# IQOV-162_Evo_Board.net
KiCad netlist of a schematic drawn in EAGLE
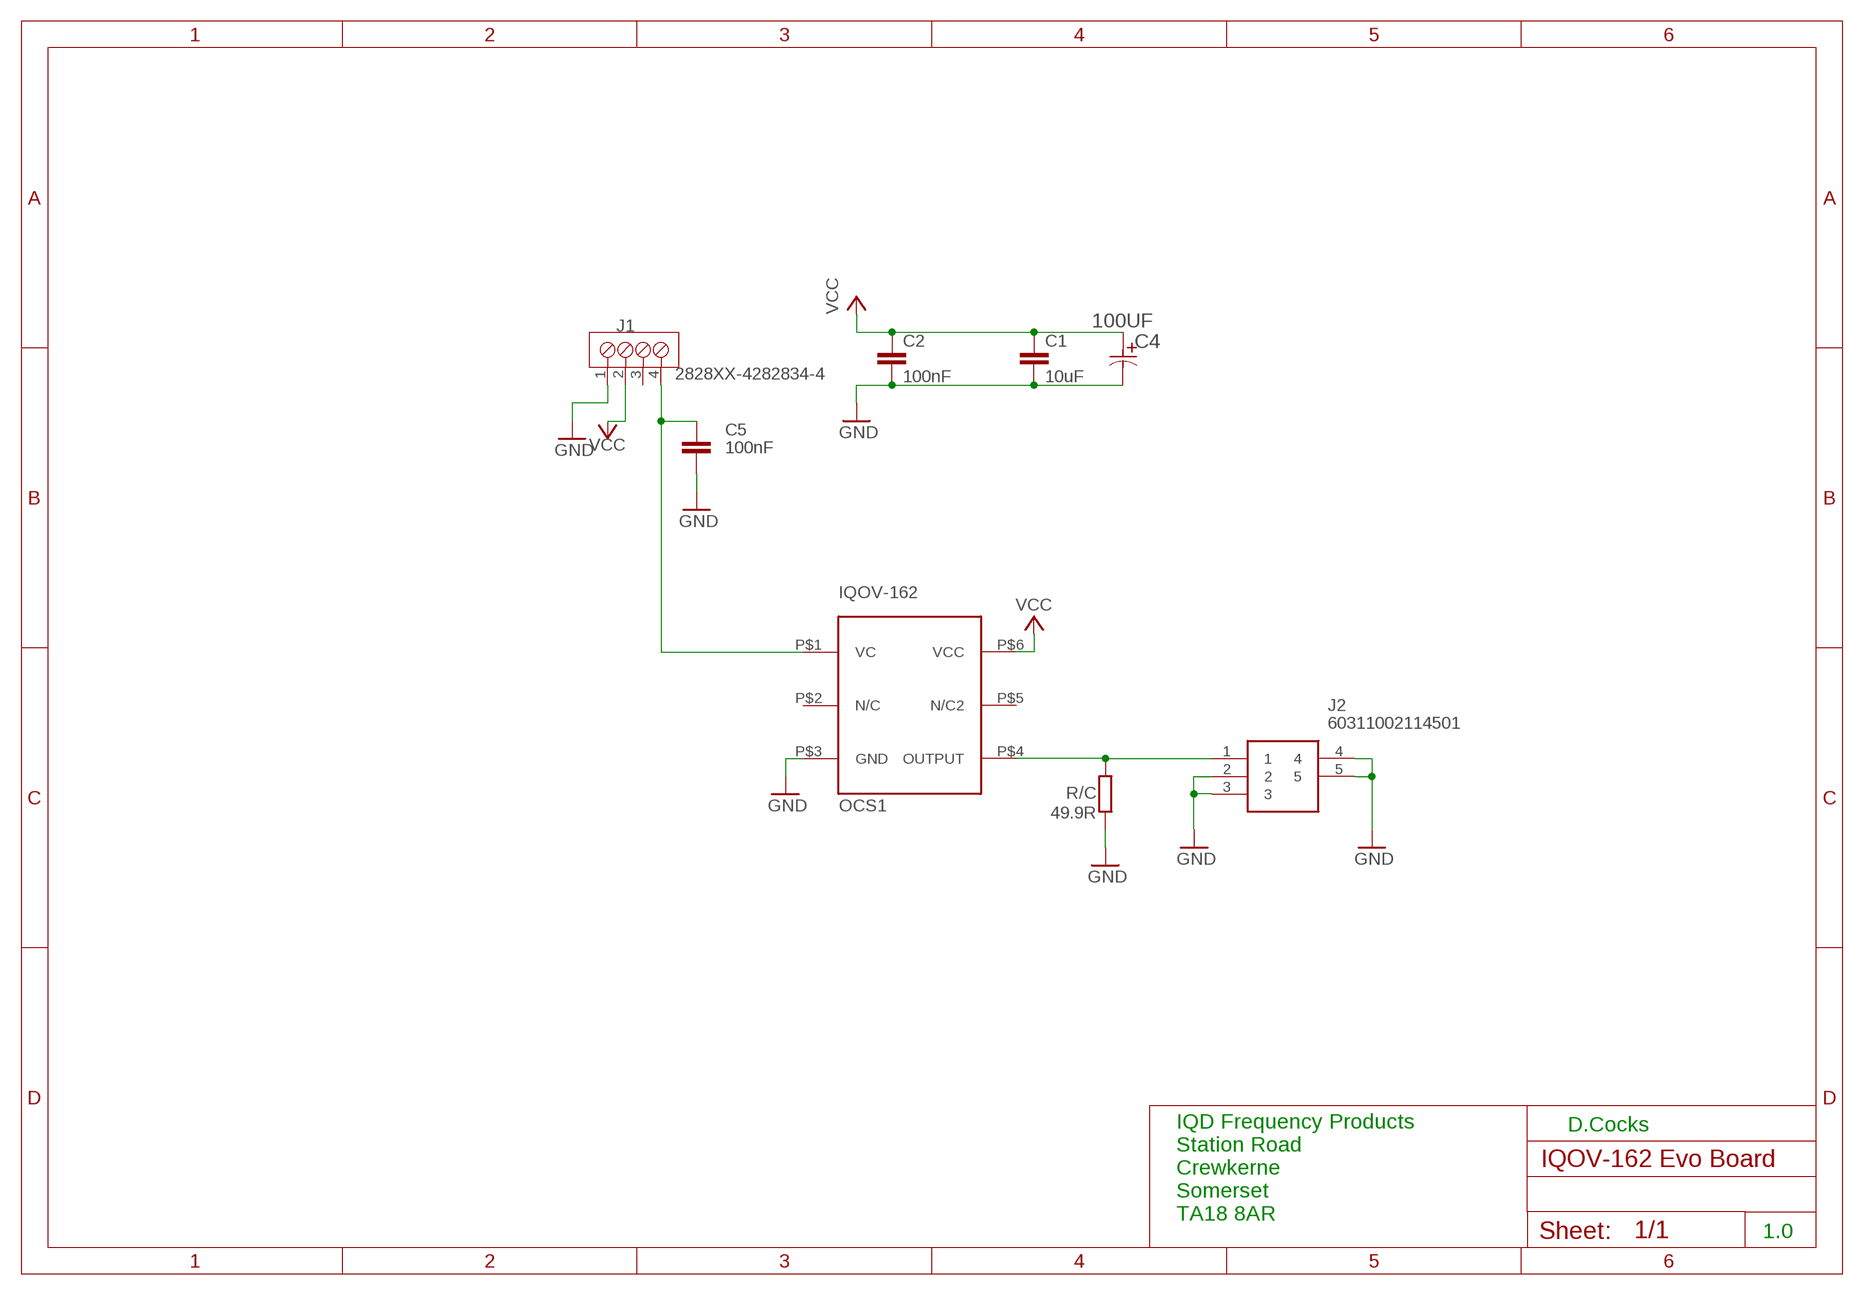
[diagram p0: schematic, sheet 1]

(export (version "E")
  (design (tool "Eeschema 10.0.6"))
  (components
    (comp (ref "C1")
      (value "10uF")
      (footprint "eagle-import:C0805")
      (libsource (lib "eagle-import") (part "C-EUC0805"))
    )
    (comp (ref "C2")
      (value "100nF")
      (footprint "eagle-import:C0805")
      (libsource (lib "eagle-import") (part "C-EUC0805"))
    )
    (comp (ref "C4")
      (value "100UF")
      (footprint "eagle-import:CAPAE530X610N")
      (fields (field (name "MPN") "EEE-FK0J101UR") (field (name "TOLERANCE") "±20 %"))
      (libsource (lib "eagle-import") (part "EEE--CASE-CFK0J101UR"))
    )
    (comp (ref "C5")
      (value "100nF")
      (footprint "eagle-import:C0805")
      (libsource (lib "eagle-import") (part "C-EUC0805"))
    )
    (comp (ref "J1")
      (value "2828XX-4282834-4")
      (footprint "eagle-import:TERMBLK_254-4N")
      (fields (field (name "MANUFACTURER") "TE Connectivity AMP Connectors") (field (name "MPN") "282834-4"))
      (libsource (lib "eagle-import") (part "2828XX-4282834-4"))
    )
    (comp (ref "J2")
      (value "60311002114501")
      (footprint "eagle-import:60312002114503")
      (fields
        (field (name "MANUFACTURER_PART_NUMBER") "60312002114503")
        (field (name "MOUSER_PART_NUMBER") "710-60312002114503")
      )
      (libsource (lib "eagle-import") (part "60312002114503"))
    )
    (comp (ref "OCS1")
      (value "IQOV-162")
      (footprint "eagle-import:IQOV-162")
      (libsource (lib "eagle-import") (part "IQOV-162"))
    )
    (comp (ref "R/C")
      (value "49.9R")
      (footprint "eagle-import:M1206")
      (libsource (lib "eagle-import") (part "R-EU_M1206"))
    )
  )
  (nets
    (net (code "1") (name "GND") (class "Default")
      (node (ref "C1") (pin "2") (pinfunction "2_2") (pintype "passive"))
      (node (ref "C2") (pin "2") (pinfunction "2_2") (pintype "passive"))
      (node (ref "C4") (pin "2") (pinfunction "2_2") (pintype "passive"))
      (node (ref "C5") (pin "2") (pinfunction "2_2") (pintype "passive"))
      (node (ref "J1") (pin "1") (pinfunction "1_1") (pintype "bidirectional"))
      (node (ref "J2") (pin "2") (pinfunction "2_2") (pintype "bidirectional"))
      (node (ref "J2") (pin "3") (pinfunction "3_3") (pintype "bidirectional"))
      (node (ref "J2") (pin "4") (pinfunction "4_4") (pintype "bidirectional"))
      (node (ref "J2") (pin "5") (pinfunction "5_5") (pintype "bidirectional"))
      (node (ref "OCS1") (pin "P$3") (pinfunction "GND_P$3") (pintype "bidirectional"))
      (node (ref "R/C") (pin "1") (pinfunction "1_1") (pintype "passive"))
    )
    (net (code "2") (name "Net-(OCS1-OUTPUT)") (class "Default")
      (node (ref "J2") (pin "1") (pinfunction "1_1") (pintype "bidirectional"))
      (node (ref "OCS1") (pin "P$4") (pinfunction "OUTPUT_P$4") (pintype "bidirectional"))
      (node (ref "R/C") (pin "2") (pinfunction "2_2") (pintype "passive"))
    )
    (net (code "3") (name "Net-(OCS1-VC)") (class "Default")
      (node (ref "C5") (pin "1") (pinfunction "1_1") (pintype "passive"))
      (node (ref "J1") (pin "4") (pinfunction "4_4") (pintype "bidirectional"))
      (node (ref "OCS1") (pin "P$1") (pinfunction "VC_P$1") (pintype "bidirectional"))
    )
    (net (code "4") (name "VCC") (class "Default")
      (node (ref "C1") (pin "1") (pinfunction "1_1") (pintype "passive"))
      (node (ref "C2") (pin "1") (pinfunction "1_1") (pintype "passive"))
      (node (ref "C4") (pin "1") (pinfunction "1_1") (pintype "passive"))
      (node (ref "J1") (pin "2") (pinfunction "2_2") (pintype "bidirectional"))
      (node (ref "OCS1") (pin "P$6") (pinfunction "VCC_P$6") (pintype "bidirectional"))
    )
    (net (code "5") (name "unconnected-(J1-Pad3)") (class "Default")
      (node (ref "J1") (pin "3") (pinfunction "3_3") (pintype "bidirectional"))
    )
    (net (code "6") (name "unconnected-(OCS1-N{slash}C-PadP$2)") (class "Default")
      (node (ref "OCS1") (pin "P$2") (pinfunction "N/C_P$2") (pintype "bidirectional"))
    )
    (net (code "7") (name "unconnected-(OCS1-N{slash}C2-PadP$5)") (class "Default")
      (node (ref "OCS1") (pin "P$5") (pinfunction "N/C2_P$5") (pintype "bidirectional"))
    )
  )
)
